# analog.net
KiCad netlist of a schematic drawn in EAGLE
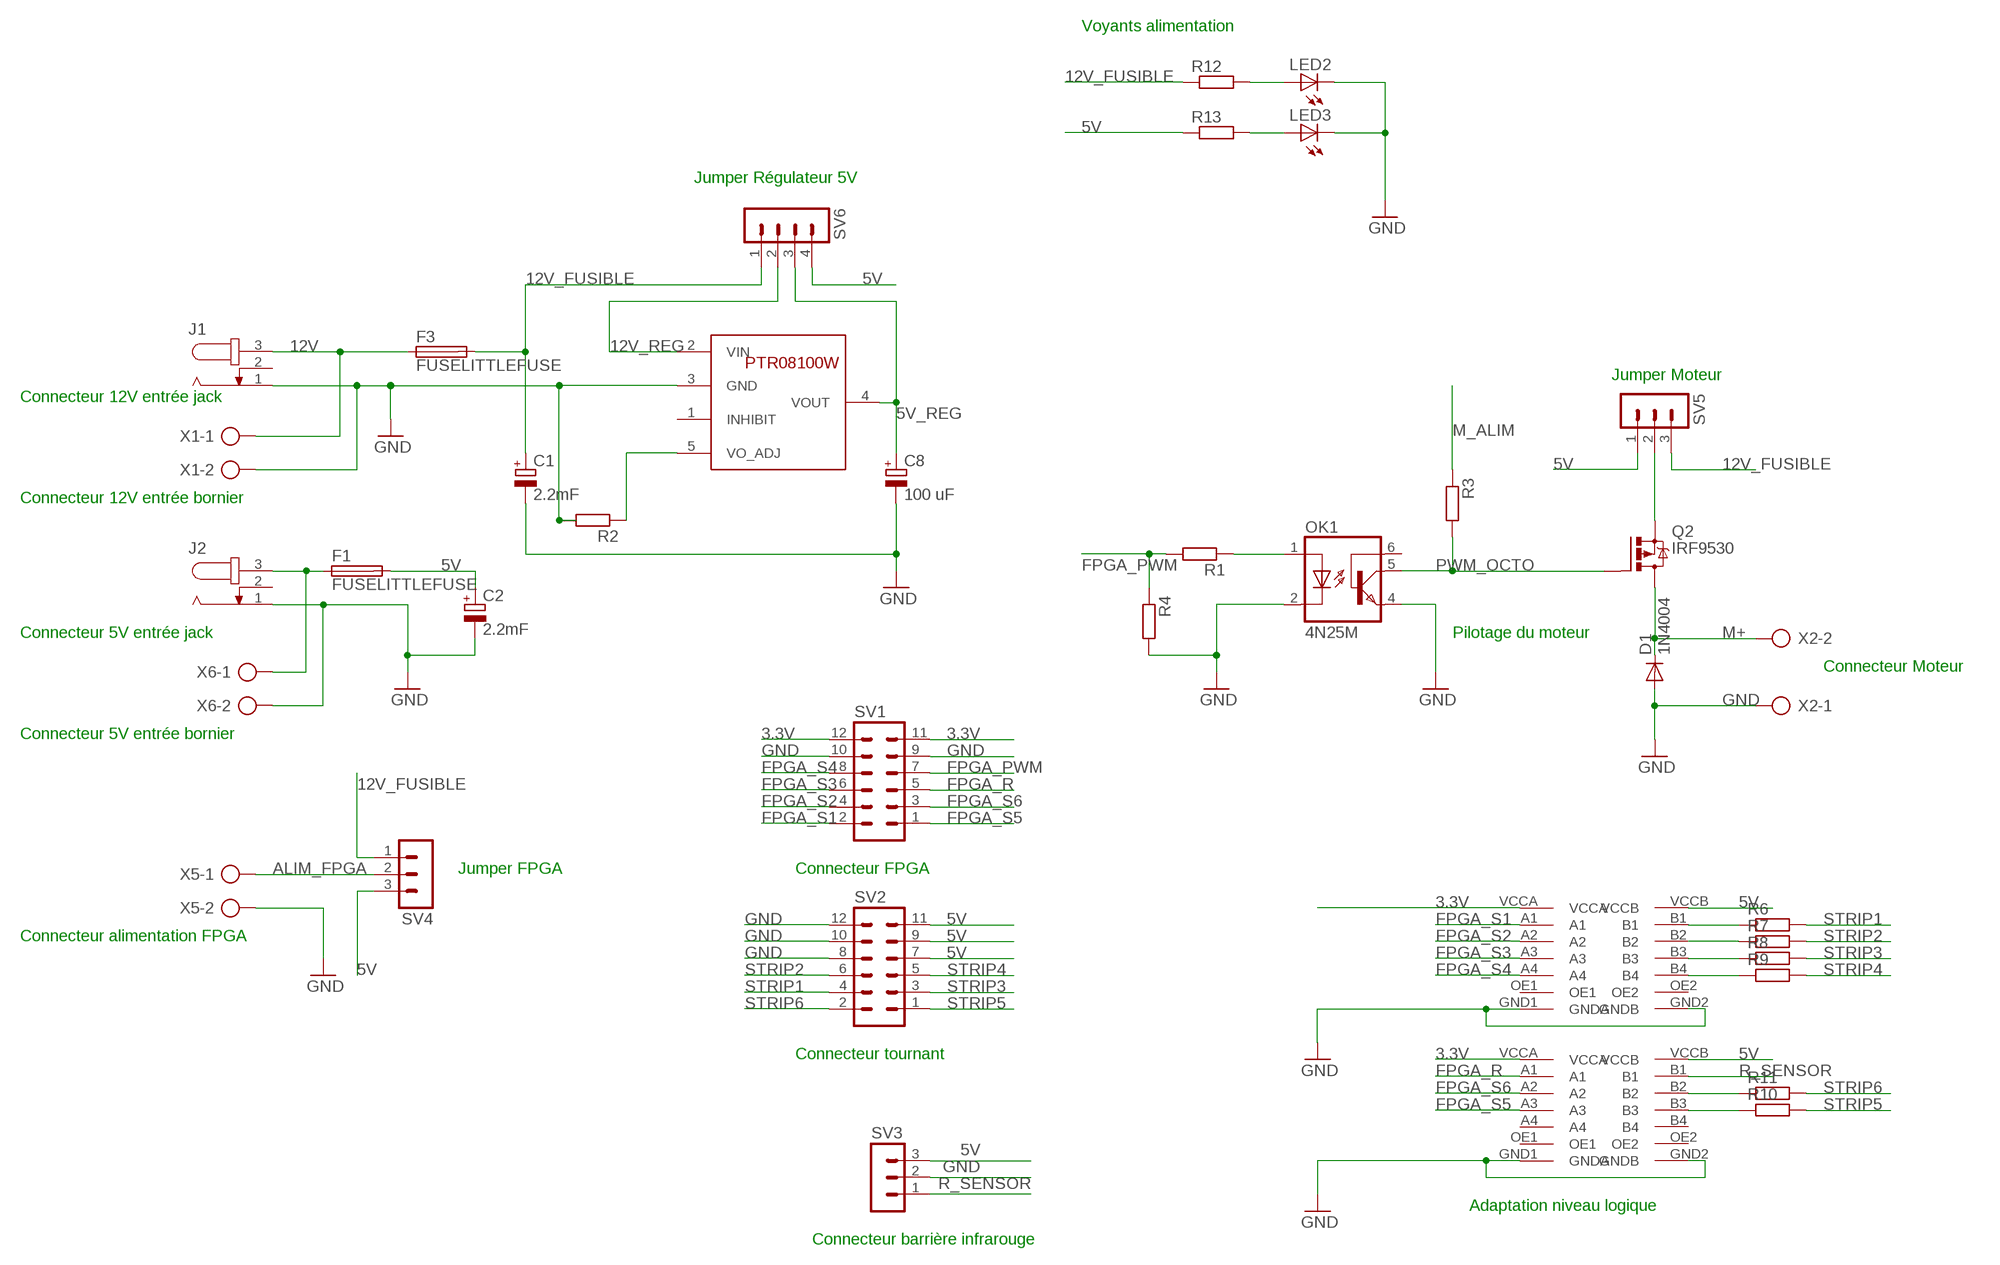
[diagram p0: schematic, sheet 1]

(export (version "E")
  (design (tool "Eeschema 10.0.6"))
  (components
    (comp (ref "C1")
      (value "2.2mF")
      (footprint "eagle-import:E7,5-16")
      (libsource (lib "eagle-import") (part "CPOL-EUE7.5-16"))
    )
    (comp (ref "C2")
      (value "2.2mF")
      (footprint "eagle-import:E7,5-16")
      (libsource (lib "eagle-import") (part "CPOL-EUE7.5-16"))
    )
    (comp (ref "C8")
      (value "100 uF")
      (footprint "eagle-import:E2,5-7")
      (libsource (lib "eagle-import") (part "CPOL-EUE2.5-7"))
    )
    (comp (ref "D1")
      (value "1N4004")
      (footprint "eagle-import:DO41-10")
      (libsource (lib "eagle-import") (part "1N4004"))
    )
    (comp (ref "F1")
      (value "FUSELITTLEFUSE")
      (footprint "eagle-import:LITTLEFUSE")
      (fields (field (name "OC_FARNELL") "unknown") (field (name "OC_NEWARK") "unknown"))
      (libsource (lib "eagle-import") (part "FUSELITTLEFUSE"))
    )
    (comp (ref "F3")
      (value "FUSELITTLEFUSE")
      (footprint "eagle-import:LITTLEFUSE")
      (libsource (lib "eagle-import") (part "FUSELITTLEFUSE"))
    )
    (comp (ref "J1")
      (value "JACK-PLUG1")
      (footprint "eagle-import:SPC4078")
      (libsource (lib "eagle-import") (part "JACK-PLUG1"))
    )
    (comp (ref "J2")
      (value "JACK-PLUG1")
      (footprint "eagle-import:SPC4078")
      (fields (field (name "OC_FARNELL") "unknown") (field (name "OC_NEWARK") "unknown"))
      (libsource (lib "eagle-import") (part "JACK-PLUG1"))
    )
    (comp (ref "LED2")
      (value "LED5MM")
      (footprint "eagle-import:LED5MM")
      (libsource (lib "eagle-import") (part "LED5MM"))
    )
    (comp (ref "LED3")
      (value "LED5MM")
      (footprint "eagle-import:LED5MM")
      (libsource (lib "eagle-import") (part "LED5MM"))
    )
    (comp (ref "OK1")
      (value "4N25M")
      (footprint "eagle-import:DIL06")
      (fields
        (field (name "MPN") "4N25-M")
        (field (name "MPN_1") "4N25-M")
        (field (name "OC_FARNELL") "1021349")
        (field (name "OC_NEWARK") "98K9084")
      )
      (libsource (lib "eagle-import") (part "4N?M25"))
    )
    (comp (ref "Q2")
      (value "IRF9530")
      (footprint "eagle-import:TO220BV")
      (libsource (lib "eagle-import") (part "IRF9530"))
    )
    (comp (ref "R1")
      (value "R-EU_0207/10")
      (footprint "eagle-import:0207_10")
      (libsource (lib "eagle-import") (part "R-EU_0207/10"))
    )
    (comp (ref "R2")
      (value "R-EU_0207/10")
      (footprint "eagle-import:0207_10")
      (libsource (lib "eagle-import") (part "R-EU_0207/10"))
    )
    (comp (ref "R3")
      (value "R-EU_0207/10")
      (footprint "eagle-import:0207_10")
      (libsource (lib "eagle-import") (part "R-EU_0207/10"))
    )
    (comp (ref "R4")
      (value "R-EU_0207/10")
      (footprint "eagle-import:0207_10")
      (libsource (lib "eagle-import") (part "R-EU_0207/10"))
    )
    (comp (ref "R6")
      (value "R-EU_0207/10")
      (footprint "eagle-import:0207_10")
      (libsource (lib "eagle-import") (part "R-EU_0207/10"))
    )
    (comp (ref "R7")
      (value "R-EU_0207/10")
      (footprint "eagle-import:0207_10")
      (libsource (lib "eagle-import") (part "R-EU_0207/10"))
    )
    (comp (ref "R8")
      (value "R-EU_0207/10")
      (footprint "eagle-import:0207_10")
      (libsource (lib "eagle-import") (part "R-EU_0207/10"))
    )
    (comp (ref "R9")
      (value "R-EU_0207/10")
      (footprint "eagle-import:0207_10")
      (libsource (lib "eagle-import") (part "R-EU_0207/10"))
    )
    (comp (ref "R10")
      (value "R-EU_0207/10")
      (footprint "eagle-import:0207_10")
      (libsource (lib "eagle-import") (part "R-EU_0207/10"))
    )
    (comp (ref "R11")
      (value "R-EU_0207/10")
      (footprint "eagle-import:0207_10")
      (libsource (lib "eagle-import") (part "R-EU_0207/10"))
    )
    (comp (ref "R12")
      (value "R-EU_0207/10")
      (footprint "eagle-import:0207_10")
      (libsource (lib "eagle-import") (part "R-EU_0207/10"))
    )
    (comp (ref "R13")
      (value "R-EU_0207/10")
      (footprint "eagle-import:0207_10")
      (libsource (lib "eagle-import") (part "R-EU_0207/10"))
    )
    (comp (ref "SV1")
      (value "MA06-2")
      (footprint "eagle-import:MA06-2")
      (libsource (lib "eagle-import") (part "MA06-2"))
    )
    (comp (ref "SV2")
      (value "MA06-2")
      (footprint "eagle-import:MA06-2")
      (fields (field (name "OC_FARNELL") "unknown") (field (name "OC_NEWARK") "unknown"))
      (libsource (lib "eagle-import") (part "MA06-2"))
    )
    (comp (ref "SV3")
      (value "MA03-1")
      (footprint "eagle-import:MA03-1")
      (libsource (lib "eagle-import") (part "MA03-1"))
    )
    (comp (ref "SV4")
      (value "MA03-1")
      (footprint "eagle-import:MA03-1")
      (libsource (lib "eagle-import") (part "MA03-1"))
    )
    (comp (ref "SV5")
      (value "MA03-1")
      (footprint "eagle-import:MA03-1")
      (libsource (lib "eagle-import") (part "MA03-1"))
    )
    (comp (ref "SV6")
      (value "MA04-1")
      (footprint "eagle-import:MA04-1")
      (libsource (lib "eagle-import") (part "MA04-1"))
    )
    (comp (ref "U$1")
      (value "TXB0104")
      (footprint "eagle-import:TXB0104")
      (libsource (lib "eagle-import") (part "TXB0104"))
    )
    (comp (ref "U$2")
      (value "TXB0104")
      (footprint "eagle-import:TXB0104")
      (libsource (lib "eagle-import") (part "TXB0104"))
    )
    (comp (ref "U2")
      (value "PTR08100W")
      (footprint "eagle-import:PTR08100W")
      (libsource (lib "eagle-import") (part "PTR08100W"))
    )
    (comp (ref "X1")
      (value "AK500/2")
      (footprint "eagle-import:AK500_2")
      (libsource (lib "eagle-import") (part "AK500/2"))
    )
    (comp (ref "X2")
      (value "AK500/2")
      (footprint "eagle-import:AK500_2")
      (libsource (lib "eagle-import") (part "AK500/2"))
    )
    (comp (ref "X5")
      (value "AK500/2")
      (footprint "eagle-import:AK500_2")
      (fields (field (name "OC_FARNELL") "unknown") (field (name "OC_NEWARK") "unknown"))
      (libsource (lib "eagle-import") (part "AK500/2"))
    )
    (comp (ref "X6")
      (value "AK500/2")
      (footprint "eagle-import:AK500_2")
      (fields (field (name "OC_FARNELL") "unknown") (field (name "OC_NEWARK") "unknown"))
      (libsource (lib "eagle-import") (part "AK500/2"))
    )
  )
  (nets
    (net (code "1") (name "/3.3V") (class "Default")
      (node (ref "SV1") (pin "11") (pinfunction "11_11") (pintype "passive"))
      (node (ref "SV1") (pin "12") (pinfunction "12_12") (pintype "passive"))
      (node (ref "U$1") (pin "VCCA") (pinfunction "VCCA_VCCA") (pintype "bidirectional"))
      (node (ref "U$2") (pin "VCCA") (pinfunction "VCCA_VCCA") (pintype "bidirectional"))
    )
    (net (code "2") (name "/5V") (class "Default")
      (node (ref "C2") (pin "+") (pinfunction "+_+") (pintype "passive"))
      (node (ref "F1") (pin "2") (pinfunction "2_2") (pintype "passive"))
      (node (ref "R13") (pin "1") (pinfunction "1_1") (pintype "passive"))
      (node (ref "SV2") (pin "11") (pinfunction "11_11") (pintype "passive"))
      (node (ref "SV2") (pin "7") (pinfunction "7_7") (pintype "passive"))
      (node (ref "SV2") (pin "9") (pinfunction "9_9") (pintype "passive"))
      (node (ref "SV3") (pin "3") (pinfunction "3_3") (pintype "passive"))
      (node (ref "SV4") (pin "3") (pinfunction "3_3") (pintype "passive"))
      (node (ref "SV5") (pin "1") (pinfunction "1_1") (pintype "passive"))
      (node (ref "SV6") (pin "4") (pinfunction "4_4") (pintype "passive"))
      (node (ref "U$1") (pin "VCCB") (pinfunction "VCCB_VCCB") (pintype "bidirectional"))
      (node (ref "U$2") (pin "VCCB") (pinfunction "VCCB_VCCB") (pintype "bidirectional"))
    )
    (net (code "3") (name "/5V_REG") (class "Default")
      (node (ref "C8") (pin "+") (pinfunction "+_+") (pintype "passive"))
      (node (ref "SV6") (pin "3") (pinfunction "3_3") (pintype "passive"))
      (node (ref "U2") (pin "4") (pinfunction "VOUT_4") (pintype "bidirectional"))
    )
    (net (code "4") (name "/12V") (class "Default")
      (node (ref "F3") (pin "1") (pinfunction "1_1") (pintype "passive"))
      (node (ref "J1") (pin "3") (pinfunction "3_3") (pintype "passive"))
      (node (ref "X1") (pin "1") (pinfunction "KL_1") (pintype "passive"))
    )
    (net (code "5") (name "/12V_FUSIBLE") (class "Default")
      (node (ref "C1") (pin "+") (pinfunction "+_+") (pintype "passive"))
      (node (ref "F3") (pin "2") (pinfunction "2_2") (pintype "passive"))
      (node (ref "R12") (pin "1") (pinfunction "1_1") (pintype "passive"))
      (node (ref "SV4") (pin "1") (pinfunction "1_1") (pintype "passive"))
      (node (ref "SV5") (pin "3") (pinfunction "3_3") (pintype "passive"))
      (node (ref "SV6") (pin "1") (pinfunction "1_1") (pintype "passive"))
    )
    (net (code "6") (name "/12V_REG") (class "Default")
      (node (ref "SV6") (pin "2") (pinfunction "2_2") (pintype "passive"))
      (node (ref "U2") (pin "2") (pinfunction "VIN_2") (pintype "bidirectional"))
    )
    (net (code "7") (name "/ALIM_FPGA") (class "Default")
      (node (ref "SV4") (pin "2") (pinfunction "2_2") (pintype "passive"))
      (node (ref "X5") (pin "1") (pinfunction "KL_1") (pintype "passive"))
    )
    (net (code "8") (name "/FPGA_PWM") (class "Default")
      (node (ref "R1") (pin "2") (pinfunction "2_2") (pintype "passive"))
      (node (ref "R4") (pin "1") (pinfunction "1_1") (pintype "passive"))
      (node (ref "SV1") (pin "7") (pinfunction "7_7") (pintype "passive"))
    )
    (net (code "9") (name "/FPGA_R") (class "Default")
      (node (ref "SV1") (pin "5") (pinfunction "5_5") (pintype "passive"))
      (node (ref "U$2") (pin "A1") (pinfunction "A1_A1") (pintype "bidirectional"))
    )
    (net (code "10") (name "/FPGA_S1") (class "Default")
      (node (ref "SV1") (pin "2") (pinfunction "2_2") (pintype "passive"))
      (node (ref "U$1") (pin "A1") (pinfunction "A1_A1") (pintype "bidirectional"))
    )
    (net (code "11") (name "/FPGA_S2") (class "Default")
      (node (ref "SV1") (pin "4") (pinfunction "4_4") (pintype "passive"))
      (node (ref "U$1") (pin "A2") (pinfunction "A2_A2") (pintype "bidirectional"))
    )
    (net (code "12") (name "/FPGA_S3") (class "Default")
      (node (ref "SV1") (pin "6") (pinfunction "6_6") (pintype "passive"))
      (node (ref "U$1") (pin "A3") (pinfunction "A3_A3") (pintype "bidirectional"))
    )
    (net (code "13") (name "/FPGA_S4") (class "Default")
      (node (ref "SV1") (pin "8") (pinfunction "8_8") (pintype "passive"))
      (node (ref "U$1") (pin "A4") (pinfunction "A4_A4") (pintype "bidirectional"))
    )
    (net (code "14") (name "/FPGA_S5") (class "Default")
      (node (ref "SV1") (pin "1") (pinfunction "1_1") (pintype "passive"))
      (node (ref "U$2") (pin "A3") (pinfunction "A3_A3") (pintype "bidirectional"))
    )
    (net (code "15") (name "/FPGA_S6") (class "Default")
      (node (ref "SV1") (pin "3") (pinfunction "3_3") (pintype "passive"))
      (node (ref "U$2") (pin "A2") (pinfunction "A2_A2") (pintype "bidirectional"))
    )
    (net (code "16") (name "/M+") (class "Default")
      (node (ref "D1") (pin "C") (pinfunction "C_C") (pintype "passive"))
      (node (ref "Q2") (pin "D") (pinfunction "D_D") (pintype "passive"))
      (node (ref "X2") (pin "2") (pinfunction "KL_2") (pintype "passive"))
    )
    (net (code "17") (name "/M_ALIM") (class "Default")
      (node (ref "Q2") (pin "S") (pinfunction "S_S") (pintype "passive"))
      (node (ref "R3") (pin "1") (pinfunction "1_1") (pintype "passive"))
      (node (ref "SV5") (pin "2") (pinfunction "2_2") (pintype "passive"))
    )
    (net (code "18") (name "/PWM_OCTO") (class "Default")
      (node (ref "OK1") (pin "5") (pinfunction "COL_5") (pintype "passive"))
      (node (ref "Q2") (pin "G") (pinfunction "G_G") (pintype "passive"))
      (node (ref "R3") (pin "2") (pinfunction "2_2") (pintype "passive"))
    )
    (net (code "19") (name "/R_SENSOR") (class "Default")
      (node (ref "SV3") (pin "1") (pinfunction "1_1") (pintype "passive"))
      (node (ref "U$2") (pin "B1") (pinfunction "B1_B1") (pintype "bidirectional"))
    )
    (net (code "20") (name "/STRIP1") (class "Default")
      (node (ref "R6") (pin "2") (pinfunction "2_2") (pintype "passive"))
      (node (ref "SV2") (pin "4") (pinfunction "4_4") (pintype "passive"))
    )
    (net (code "21") (name "/STRIP2") (class "Default")
      (node (ref "R7") (pin "2") (pinfunction "2_2") (pintype "passive"))
      (node (ref "SV2") (pin "6") (pinfunction "6_6") (pintype "passive"))
    )
    (net (code "22") (name "/STRIP3") (class "Default")
      (node (ref "R8") (pin "2") (pinfunction "2_2") (pintype "passive"))
      (node (ref "SV2") (pin "3") (pinfunction "3_3") (pintype "passive"))
    )
    (net (code "23") (name "/STRIP4") (class "Default")
      (node (ref "R9") (pin "2") (pinfunction "2_2") (pintype "passive"))
      (node (ref "SV2") (pin "5") (pinfunction "5_5") (pintype "passive"))
    )
    (net (code "24") (name "/STRIP5") (class "Default")
      (node (ref "R10") (pin "2") (pinfunction "2_2") (pintype "passive"))
      (node (ref "SV2") (pin "1") (pinfunction "1_1") (pintype "passive"))
    )
    (net (code "25") (name "/STRIP6") (class "Default")
      (node (ref "R11") (pin "2") (pinfunction "2_2") (pintype "passive"))
      (node (ref "SV2") (pin "2") (pinfunction "2_2") (pintype "passive"))
    )
    (net (code "26") (name "GND") (class "Default")
      (node (ref "C1") (pin "-") (pinfunction "-_-") (pintype "passive"))
      (node (ref "C2") (pin "-") (pinfunction "-_-") (pintype "passive"))
      (node (ref "C8") (pin "-") (pinfunction "-_-") (pintype "passive"))
      (node (ref "D1") (pin "A") (pinfunction "A_A") (pintype "passive"))
      (node (ref "J1") (pin "1") (pinfunction "1_1") (pintype "passive"))
      (node (ref "J2") (pin "1") (pinfunction "1_1") (pintype "passive"))
      (node (ref "LED2") (pin "K") (pinfunction "C_K") (pintype "passive"))
      (node (ref "LED3") (pin "K") (pinfunction "C_K") (pintype "passive"))
      (node (ref "OK1") (pin "2") (pinfunction "C_2") (pintype "passive"))
      (node (ref "OK1") (pin "4") (pinfunction "EMI_4") (pintype "passive"))
      (node (ref "R2") (pin "2") (pinfunction "2_2") (pintype "passive"))
      (node (ref "R4") (pin "2") (pinfunction "2_2") (pintype "passive"))
      (node (ref "SV1") (pin "10") (pinfunction "10_10") (pintype "passive"))
      (node (ref "SV1") (pin "9") (pinfunction "9_9") (pintype "passive"))
      (node (ref "SV2") (pin "10") (pinfunction "10_10") (pintype "passive"))
      (node (ref "SV2") (pin "12") (pinfunction "12_12") (pintype "passive"))
      (node (ref "SV2") (pin "8") (pinfunction "8_8") (pintype "passive"))
      (node (ref "SV3") (pin "2") (pinfunction "2_2") (pintype "passive"))
      (node (ref "U$1") (pin "GND1") (pinfunction "GNDA_GND1") (pintype "bidirectional"))
      (node (ref "U$1") (pin "GND2") (pinfunction "GNDB_GND2") (pintype "bidirectional"))
      (node (ref "U$2") (pin "GND1") (pinfunction "GNDA_GND1") (pintype "bidirectional"))
      (node (ref "U$2") (pin "GND2") (pinfunction "GNDB_GND2") (pintype "bidirectional"))
      (node (ref "U2") (pin "3") (pinfunction "GND_3") (pintype "bidirectional"))
      (node (ref "X1") (pin "2") (pinfunction "KL_2") (pintype "passive"))
      (node (ref "X2") (pin "1") (pinfunction "KL_1") (pintype "passive"))
      (node (ref "X5") (pin "2") (pinfunction "KL_2") (pintype "passive"))
      (node (ref "X6") (pin "2") (pinfunction "KL_2") (pintype "passive"))
    )
    (net (code "27") (name "Net-(LED2-PadA)") (class "Default")
      (node (ref "LED2") (pin "A") (pinfunction "A_A") (pintype "passive"))
      (node (ref "R12") (pin "2") (pinfunction "2_2") (pintype "passive"))
    )
    (net (code "28") (name "Net-(LED3-PadA)") (class "Default")
      (node (ref "LED3") (pin "A") (pinfunction "A_A") (pintype "passive"))
      (node (ref "R13") (pin "2") (pinfunction "2_2") (pintype "passive"))
    )
    (net (code "29") (name "Net-(OK1-A)") (class "Default")
      (node (ref "OK1") (pin "1") (pinfunction "A_1") (pintype "passive"))
      (node (ref "R1") (pin "1") (pinfunction "1_1") (pintype "passive"))
    )
    (net (code "30") (name "Net-(R6-Pad1)") (class "Default")
      (node (ref "R6") (pin "1") (pinfunction "1_1") (pintype "passive"))
      (node (ref "U$1") (pin "B1") (pinfunction "B1_B1") (pintype "bidirectional"))
    )
    (net (code "31") (name "Net-(R7-Pad1)") (class "Default")
      (node (ref "R7") (pin "1") (pinfunction "1_1") (pintype "passive"))
      (node (ref "U$1") (pin "B2") (pinfunction "B2_B2") (pintype "bidirectional"))
    )
    (net (code "32") (name "Net-(R8-Pad1)") (class "Default")
      (node (ref "R8") (pin "1") (pinfunction "1_1") (pintype "passive"))
      (node (ref "U$1") (pin "B3") (pinfunction "B3_B3") (pintype "bidirectional"))
    )
    (net (code "33") (name "Net-(R9-Pad1)") (class "Default")
      (node (ref "R9") (pin "1") (pinfunction "1_1") (pintype "passive"))
      (node (ref "U$1") (pin "B4") (pinfunction "B4_B4") (pintype "bidirectional"))
    )
    (net (code "34") (name "Net-(R10-Pad1)") (class "Default")
      (node (ref "R10") (pin "1") (pinfunction "1_1") (pintype "passive"))
      (node (ref "U$2") (pin "B3") (pinfunction "B3_B3") (pintype "bidirectional"))
    )
    (net (code "35") (name "Net-(R11-Pad1)") (class "Default")
      (node (ref "R11") (pin "1") (pinfunction "1_1") (pintype "passive"))
      (node (ref "U$2") (pin "B2") (pinfunction "B2_B2") (pintype "bidirectional"))
    )
    (net (code "36") (name "Net-(U2-VO_ADJ)") (class "Default")
      (node (ref "R2") (pin "1") (pinfunction "1_1") (pintype "passive"))
      (node (ref "U2") (pin "5") (pinfunction "VO_ADJ_5") (pintype "bidirectional"))
    )
    (net (code "37") (name "Net-(X6A-KL)") (class "Default")
      (node (ref "F1") (pin "1") (pinfunction "1_1") (pintype "passive"))
      (node (ref "J2") (pin "3") (pinfunction "3_3") (pintype "passive"))
      (node (ref "X6") (pin "1") (pinfunction "KL_1") (pintype "passive"))
    )
    (net (code "38") (name "unconnected-(J1-Pad2)") (class "Default")
      (node (ref "J1") (pin "2") (pinfunction "2_2") (pintype "passive"))
    )
    (net (code "39") (name "unconnected-(J2-Pad2)") (class "Default")
      (node (ref "J2") (pin "2") (pinfunction "2_2") (pintype "passive"))
    )
    (net (code "40") (name "unconnected-(OK1-BAS-Pad6)") (class "Default")
      (node (ref "OK1") (pin "6") (pinfunction "BAS_6") (pintype "passive"))
    )
    (net (code "41") (name "unconnected-(U$1-PadOE1)") (class "Default")
      (node (ref "U$1") (pin "OE1") (pinfunction "OE1_OE1") (pintype "bidirectional"))
    )
    (net (code "42") (name "unconnected-(U$1-PadOE2)") (class "Default")
      (node (ref "U$1") (pin "OE2") (pinfunction "OE2_OE2") (pintype "bidirectional"))
    )
    (net (code "43") (name "unconnected-(U$2-PadA4)") (class "Default")
      (node (ref "U$2") (pin "A4") (pinfunction "A4_A4") (pintype "bidirectional"))
    )
    (net (code "44") (name "unconnected-(U$2-PadB4)") (class "Default")
      (node (ref "U$2") (pin "B4") (pinfunction "B4_B4") (pintype "bidirectional"))
    )
    (net (code "45") (name "unconnected-(U$2-PadOE1)") (class "Default")
      (node (ref "U$2") (pin "OE1") (pinfunction "OE1_OE1") (pintype "bidirectional"))
    )
    (net (code "46") (name "unconnected-(U$2-PadOE2)") (class "Default")
      (node (ref "U$2") (pin "OE2") (pinfunction "OE2_OE2") (pintype "bidirectional"))
    )
    (net (code "47") (name "unconnected-(U2-INHIBIT-Pad1)") (class "Default")
      (node (ref "U2") (pin "1") (pinfunction "INHIBIT_1") (pintype "bidirectional"))
    )
  )
)
